# SAMV71_Xplained_Ultra_EDBG.net
KiCad netlist of a schematic drawn in Altium Designer
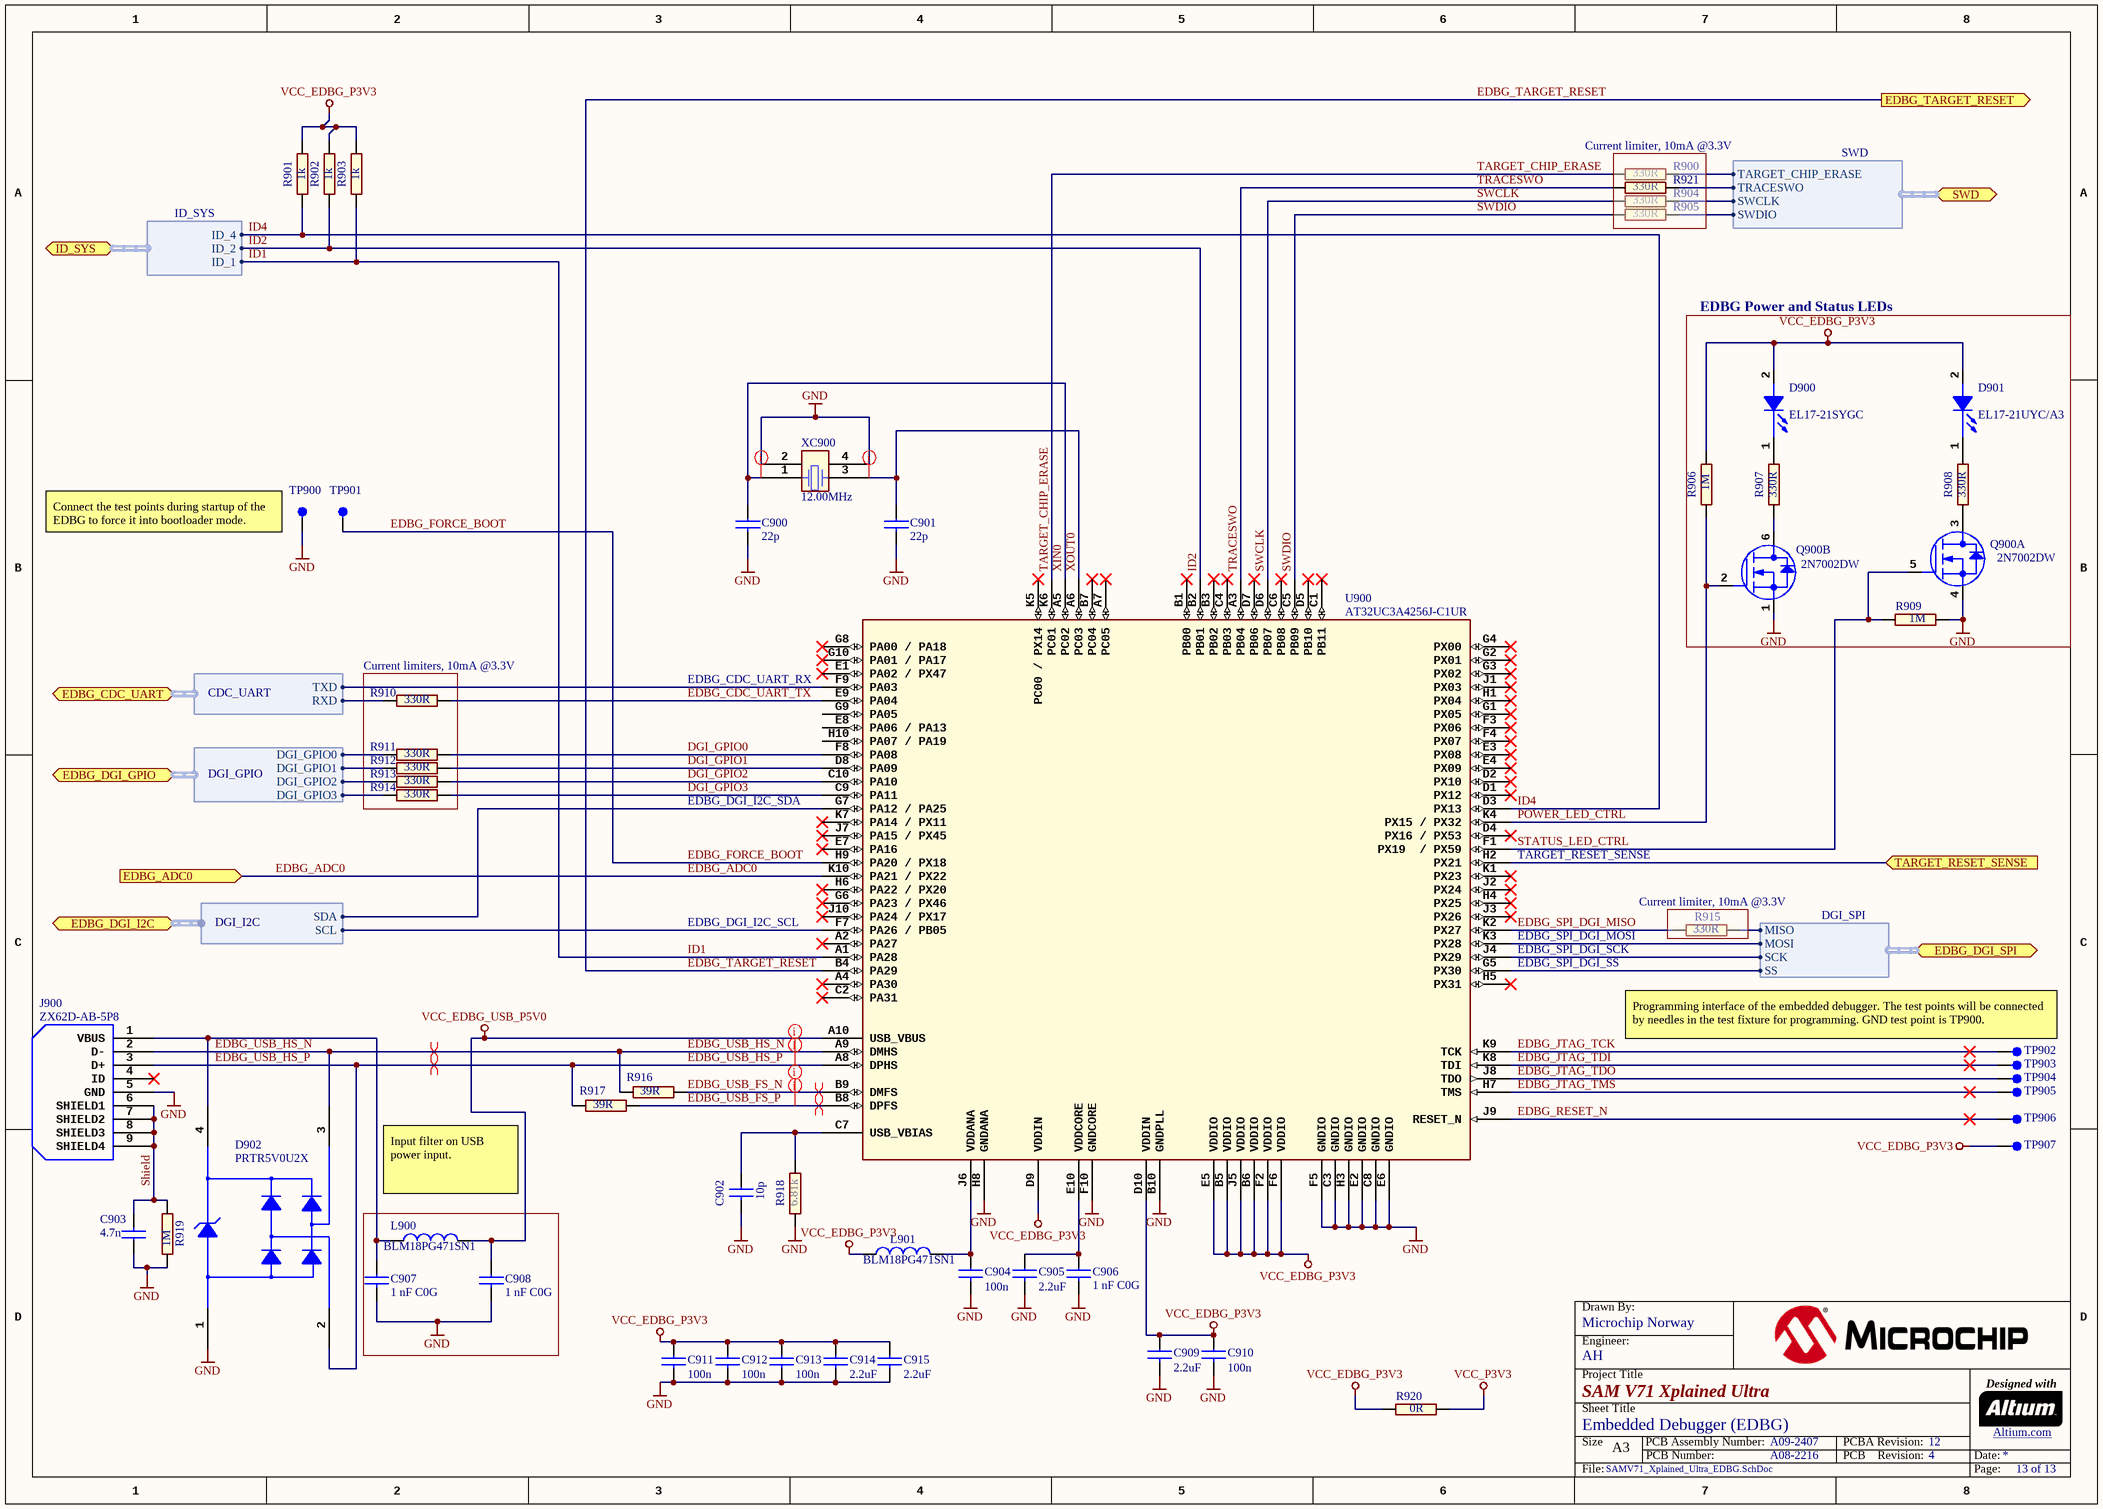
[diagram p0: SAMV71_Xplained_Ultra_EDBG.SchDoc]

(export (version "E")
  (design (tool "Eeschema 10.0.6"))
  (components
    (comp (ref "C900")
      (value "22p")
      (footprint "AP1-00053")
      (description "Ceramic capacitor, SMD 0402, NP0, 50V, +/-5%")
      (fields (field (name "TOLERANCE") "50V, +/-5%") (field (name "MANUFACTURER") "YAGEO CORP"))
      (libsource (lib "AltiumDbLib") (part "CAP-NONPOL"))
    )
    (comp (ref "C901")
      (value "22p")
      (footprint "AP1-00053")
      (description "Ceramic capacitor, SMD 0402, NP0, 50V, +/-5%")
      (fields (field (name "TOLERANCE") "50V, +/-5%") (field (name "MANUFACTURER") "YAGEO CORP"))
      (libsource (lib "AltiumDbLib") (part "CAP-NONPOL"))
    )
    (comp (ref "C902")
      (value "10p")
      (footprint "AP1-00053")
      (description "Ceramic capacitor, SMD 0402, NP0, 50V, +/-5%")
      (fields (field (name "TOLERANCE") "50V, +/-5%") (field (name "MANUFACTURER") "AVX"))
      (libsource (lib "AltiumDbLib") (part "CAP-NONPOL"))
    )
    (comp (ref "C903")
      (value "4.7n")
      (footprint "AP1-00053")
      (description "Ceramic capacitor, SMD 0402, X7R, 25V, +/-10%")
      (fields (field (name "TOLERANCE") "25V, +/-10%") (field (name "MANUFACTURER") "PHYCOMP"))
      (libsource (lib "AltiumDbLib") (part "CAP-NONPOL"))
    )
    (comp (ref "C904")
      (value "100n")
      (footprint "AP1-00053")
      (description "Ceramic capacitor, SMD 0402, X7R, 16V, +/-10%")
      (fields (field (name "TOLERANCE") "16V, +/-10%") (field (name "MANUFACTURER") "Kemet"))
      (libsource (lib "AltiumDbLib") (part "CAP-NONPOL"))
    )
    (comp (ref "C905")
      (value "2.2uF")
      (footprint "AP1-00053")
      (description "Ceramic capacitor, SMD 0402, X5R, 6.3V, +/-20%")
      (fields (field (name "TOLERANCE") "Â±20%") (field (name "MANUFACTURER") "Kemet"))
      (libsource (lib "AltiumDbLib") (part "CAP-NONPOL"))
    )
    (comp (ref "C906")
      (value "1 nF C0G")
      (footprint "AP1-00053")
      (description "Ceramic capacitor, SMD 0402, C0G, 50V, +/-5%")
      (fields (field (name "TOLERANCE") "5%") (field (name "MANUFACTURER") "Murata"))
      (libsource (lib "AltiumDbLib") (part "CAP-NONPOL"))
    )
    (comp (ref "C907")
      (value "1 nF C0G")
      (footprint "AP1-00053")
      (description "Ceramic capacitor, SMD 0402, C0G, 50V, +/-5%")
      (fields (field (name "TOLERANCE") "5%") (field (name "MANUFACTURER") "Murata"))
      (libsource (lib "AltiumDbLib") (part "CAP-NONPOL"))
    )
    (comp (ref "C908")
      (value "1 nF C0G")
      (footprint "AP1-00053")
      (description "Ceramic capacitor, SMD 0402, C0G, 50V, +/-5%")
      (fields (field (name "TOLERANCE") "5%") (field (name "MANUFACTURER") "Murata"))
      (libsource (lib "AltiumDbLib") (part "CAP-NONPOL"))
    )
    (comp (ref "C909")
      (value "2.2uF")
      (footprint "AP1-00053")
      (description "Ceramic capacitor, SMD 0402, X5R, 6.3V, +/-20%")
      (fields (field (name "TOLERANCE") "Â±20%") (field (name "MANUFACTURER") "Kemet"))
      (libsource (lib "AltiumDbLib") (part "CAP-NONPOL"))
    )
    (comp (ref "C910")
      (value "100n")
      (footprint "AP1-00053")
      (description "Ceramic capacitor, SMD 0402, X7R, 16V, +/-10%")
      (fields (field (name "TOLERANCE") "16V, +/-10%") (field (name "MANUFACTURER") "Kemet"))
      (libsource (lib "AltiumDbLib") (part "CAP-NONPOL"))
    )
    (comp (ref "C911")
      (value "100n")
      (footprint "AP1-00053")
      (description "Ceramic capacitor, SMD 0402, X7R, 16V, +/-10%")
      (fields (field (name "TOLERANCE") "16V, +/-10%") (field (name "MANUFACTURER") "Kemet"))
      (libsource (lib "AltiumDbLib") (part "CAP-NONPOL"))
    )
    (comp (ref "C912")
      (value "100n")
      (footprint "AP1-00053")
      (description "Ceramic capacitor, SMD 0402, X7R, 16V, +/-10%")
      (fields (field (name "TOLERANCE") "16V, +/-10%") (field (name "MANUFACTURER") "Kemet"))
      (libsource (lib "AltiumDbLib") (part "CAP-NONPOL"))
    )
    (comp (ref "C913")
      (value "100n")
      (footprint "AP1-00053")
      (description "Ceramic capacitor, SMD 0402, X7R, 16V, +/-10%")
      (fields (field (name "TOLERANCE") "16V, +/-10%") (field (name "MANUFACTURER") "Kemet"))
      (libsource (lib "AltiumDbLib") (part "CAP-NONPOL"))
    )
    (comp (ref "C914")
      (value "2.2uF")
      (footprint "AP1-00053")
      (description "Ceramic capacitor, SMD 0402, X5R, 6.3V, +/-20%")
      (fields (field (name "TOLERANCE") "Â±20%") (field (name "MANUFACTURER") "Kemet"))
      (libsource (lib "AltiumDbLib") (part "CAP-NONPOL"))
    )
    (comp (ref "C915")
      (value "2.2uF")
      (footprint "AP1-00053")
      (description "Ceramic capacitor, SMD 0402, X5R, 6.3V, +/-20%")
      (fields (field (name "TOLERANCE") "Â±20%") (field (name "MANUFACTURER") "Kemet"))
      (libsource (lib "AltiumDbLib") (part "CAP-NONPOL"))
    )
    (comp (ref "D900")
      (value "EL17-21SYGC")
      (footprint "AP4-00013")
      (description "LED, Green, Wave length=575nm, SMD 0805, ±70°")
      (fields (field (name "MANUFACTURER") "Everlight"))
      (libsource (lib "AltiumDbLib") (part "LED_12"))
    )
    (comp (ref "D901")
      (value "EL17-21UYC/A3")
      (footprint "AP4-00013")
      (description "LED, Yellow, Wave length=591nm, SMD 0805, ±70°")
      (fields (field (name "MANUFACTURER") "Everlight") (field (name "MPN") "17-21UYC/S530-A3/TR8"))
      (libsource (lib "AltiumDbLib") (part "LED_12"))
    )
    (comp (ref "D902")
      (value "PRTR5V0U2X")
      (footprint "AP4-00001")
      (description "Double rail-to-rail USB ESD protection diode")
      (fields (field (name "MANUFACTURER") "NXP"))
      (libsource (lib "AltiumDbLib") (part "PRTR5V0U2X"))
    )
    (comp (ref "J900")
      (value "ZX62D-AB-5P8")
      (footprint "AP8-00852")
      (description "Micro USB AB Connector, Standard SMT + DIP")
      (fields (field (name "MANUFACTURER") "HIROSE") (field (name "MPN") "ZX62D-AB-5P8(30)"))
      (libsource (lib "AltiumDbLib") (part "USB_AB"))
    )
    (comp (ref "L900")
      (value "BLM18PG471SN1")
      (footprint "AP3-00005")
      (description "SMD RF inductor 0603. Z=470Ohm (@100MHz), Max R(dc)=0.65Ohm, Max current=1A")
      (fields (field (name "MANUFACTURER") "Murata"))
      (libsource (lib "AltiumDbLib") (part "INDUCTOR"))
    )
    (comp (ref "L901")
      (value "BLM18PG471SN1")
      (footprint "AP3-00005")
      (description "SMD RF inductor 0603. Z=470Ohm (@100MHz), Max R(dc)=0.65Ohm, Max current=1A")
      (fields (field (name "MANUFACTURER") "Murata"))
      (libsource (lib "AltiumDbLib") (part "INDUCTOR"))
    )
    (comp (ref "Q900")
      (value "2N7002DW")
      (footprint "AP5-00001")
      (description "Dual N-Channel MOSFET, 60V, 115mA cont,RDS(ON) < 7.5 Ohm @50mA@5V, SOT-363")
      (fields
        (field (name "MANUFACTURER") "Fairchild")
        (field (name "Comment") "Same as 2N7002 but with two MOSFETs in one package")
      )
      (libsource (lib "AltiumDbLib") (part "MOSFET_DUAL_N_S2G2D1S1G1D2"))
    )
    (comp (ref "R900")
      (value "330R")
      (footprint "AP2-00000")
      (description "Thick film resistor, SMD 0402, 1/16W, 1%")
      (fields (field (name "TOLERANCE") "1 %") (field (name "MANUFACTURER") "ASJ"))
      (libsource (lib "") (part "R2_2"))
    )
    (comp (ref "R901")
      (value "1k")
      (footprint "AP2-00000")
      (description "Thick film resistor, SMD 0402, 1/16W, 1%")
      (fields (field (name "TOLERANCE") "1 %") (field (name "MANUFACTURER") "ASJ"))
      (libsource (lib "AltiumDbLib") (part "R2"))
    )
    (comp (ref "R902")
      (value "1k")
      (footprint "AP2-00000")
      (description "Thick film resistor, SMD 0402, 1/16W, 1%")
      (fields (field (name "TOLERANCE") "1 %") (field (name "MANUFACTURER") "ASJ"))
      (libsource (lib "AltiumDbLib") (part "R2"))
    )
    (comp (ref "R903")
      (value "1k")
      (footprint "AP2-00000")
      (description "Thick film resistor, SMD 0402, 1/16W, 1%")
      (fields (field (name "TOLERANCE") "1 %") (field (name "MANUFACTURER") "ASJ"))
      (libsource (lib "AltiumDbLib") (part "R2"))
    )
    (comp (ref "R904")
      (value "330R")
      (footprint "AP2-00000")
      (description "Thick film resistor, SMD 0402, 1/16W, 1%")
      (fields (field (name "TOLERANCE") "1 %") (field (name "MANUFACTURER") "ASJ"))
      (libsource (lib "") (part "R2_2"))
    )
    (comp (ref "R905")
      (value "330R")
      (footprint "AP2-00000")
      (description "Thick film resistor, SMD 0402, 1/16W, 1%")
      (fields (field (name "TOLERANCE") "1 %") (field (name "MANUFACTURER") "ASJ"))
      (libsource (lib "") (part "R2_2"))
    )
    (comp (ref "R906")
      (value "1M")
      (footprint "AP2-00000")
      (description "Thick film resistor, SMD 0402, 1/16W, 1%")
      (fields (field (name "TOLERANCE") "1 %") (field (name "MANUFACTURER") "ASJ"))
      (libsource (lib "AltiumDbLib") (part "R2"))
    )
    (comp (ref "R907")
      (value "330R")
      (footprint "AP2-00000")
      (description "Thick film resistor, SMD 0402, 1/16W, 1%")
      (fields (field (name "TOLERANCE") "1 %") (field (name "MANUFACTURER") "ASJ"))
      (libsource (lib "AltiumDbLib") (part "R2"))
    )
    (comp (ref "R908")
      (value "330R")
      (footprint "AP2-00000")
      (description "Thick film resistor, SMD 0402, 1/16W, 1%")
      (fields (field (name "TOLERANCE") "1 %") (field (name "MANUFACTURER") "ASJ"))
      (libsource (lib "AltiumDbLib") (part "R2"))
    )
    (comp (ref "R909")
      (value "1M")
      (footprint "AP2-00000")
      (description "Thick film resistor, SMD 0402, 1/16W, 1%")
      (fields (field (name "TOLERANCE") "1 %") (field (name "MANUFACTURER") "ASJ"))
      (libsource (lib "") (part "R2_4"))
    )
    (comp (ref "R910")
      (value "330R")
      (footprint "AP2-00000")
      (description "Thick film resistor, SMD 0402, 1/16W, 1%")
      (fields (field (name "TOLERANCE") "1 %") (field (name "MANUFACTURER") "ASJ"))
      (libsource (lib "") (part "R2_2"))
    )
    (comp (ref "R911")
      (value "330R")
      (footprint "AP2-00000")
      (description "Thick film resistor, SMD 0402, 1/16W, 1%")
      (fields (field (name "TOLERANCE") "1 %") (field (name "MANUFACTURER") "ASJ"))
      (libsource (lib "") (part "R2_2"))
    )
    (comp (ref "R912")
      (value "330R")
      (footprint "AP2-00000")
      (description "Thick film resistor, SMD 0402, 1/16W, 1%")
      (fields (field (name "TOLERANCE") "1 %") (field (name "MANUFACTURER") "ASJ"))
      (libsource (lib "") (part "R2_2"))
    )
    (comp (ref "R913")
      (value "330R")
      (footprint "AP2-00000")
      (description "Thick film resistor, SMD 0402, 1/16W, 1%")
      (fields (field (name "TOLERANCE") "1 %") (field (name "MANUFACTURER") "ASJ"))
      (libsource (lib "") (part "R2_2"))
    )
    (comp (ref "R914")
      (value "330R")
      (footprint "AP2-00000")
      (description "Thick film resistor, SMD 0402, 1/16W, 1%")
      (fields (field (name "TOLERANCE") "1 %") (field (name "MANUFACTURER") "ASJ"))
      (libsource (lib "") (part "R2_2"))
    )
    (comp (ref "R915")
      (value "330R")
      (footprint "AP2-00000")
      (description "Thick film resistor, SMD 0402, 1/16W, 1%")
      (fields (field (name "TOLERANCE") "1 %") (field (name "MANUFACTURER") "ASJ"))
      (libsource (lib "") (part "R2_2"))
    )
    (comp (ref "R916")
      (value "39R")
      (footprint "AP2-00011")
      (description "Thick film resistor, SMD 0402, 1/16W, 1%")
      (fields (field (name "TOLERANCE") "1 %") (field (name "MANUFACTURER") "ASJ"))
      (libsource (lib "") (part "R2_1"))
    )
    (comp (ref "R917")
      (value "39R")
      (footprint "AP2-00011")
      (description "Thick film resistor, SMD 0402, 1/16W, 1%")
      (fields (field (name "TOLERANCE") "1 %") (field (name "MANUFACTURER") "ASJ"))
      (libsource (lib "") (part "R2_1"))
    )
    (comp (ref "R918")
      (value "6.81k")
      (footprint "AP2-00011")
      (description "Thick film resistor, SMD 0402, 1/16W, 1%")
      (fields (field (name "TOLERANCE") "1%") (field (name "MANUFACTURER") "vishay"))
      (libsource (lib "AltiumDbLib") (part "R2"))
    )
    (comp (ref "R919")
      (value "1M")
      (footprint "AP2-00011")
      (description "Thick film resistor, SMD 0402, 1/16W, 1%")
      (fields (field (name "TOLERANCE") "1 %") (field (name "MANUFACTURER") "ASJ"))
      (libsource (lib "") (part "R2_3"))
    )
    (comp (ref "R920")
      (value "0R")
      (footprint "AP2-00000")
      (description "Thick film resistor, SMD 0402, 1/16W, 1%")
      (fields (field (name "TOLERANCE") "1 %") (field (name "MANUFACTURER") "(n/a)"))
      (libsource (lib "") (part "R2_2"))
    )
    (comp (ref "R921")
      (value "330R")
      (footprint "AP2-00000")
      (description "Thick film resistor, SMD 0402, 1/16W, 1%")
      (fields (field (name "TOLERANCE") "1 %") (field (name "MANUFACTURER") "ASJ"))
      (libsource (lib "") (part "R2_2"))
    )
    (comp (ref "TP900")
      (value "~")
      (footprint "AP8-00010")
      (description "Single SMD testpad")
      (libsource (lib "AltiumDbLib") (part "TESTPOINT"))
    )
    (comp (ref "TP901")
      (value "~")
      (footprint "AP8-00010")
      (description "Single SMD testpad")
      (libsource (lib "AltiumDbLib") (part "TESTPOINT"))
    )
    (comp (ref "TP902")
      (value "~")
      (footprint "AP8-00010")
      (description "Single SMD testpad")
      (libsource (lib "AltiumDbLib") (part "TESTPOINT"))
    )
    (comp (ref "TP903")
      (value "~")
      (footprint "AP8-00010")
      (description "Single SMD testpad")
      (libsource (lib "AltiumDbLib") (part "TESTPOINT"))
    )
    (comp (ref "TP904")
      (value "~")
      (footprint "AP8-00010")
      (description "Single SMD testpad")
      (libsource (lib "AltiumDbLib") (part "TESTPOINT"))
    )
    (comp (ref "TP905")
      (value "~")
      (footprint "AP8-00010")
      (description "Single SMD testpad")
      (libsource (lib "AltiumDbLib") (part "TESTPOINT"))
    )
    (comp (ref "TP906")
      (value "~")
      (footprint "AP8-00010")
      (description "Single SMD testpad")
      (libsource (lib "AltiumDbLib") (part "TESTPOINT"))
    )
    (comp (ref "TP907")
      (value "~")
      (footprint "AP8-00010")
      (description "Single SMD testpad")
      (libsource (lib "AltiumDbLib") (part "TESTPOINT"))
    )
    (comp (ref "U900")
      (value "AT32UC3A4256J-C1UR")
      (footprint "AP6-00206")
      (description "AVR 32-bit RISC MCU")
      (fields (field (name "MANUFACTURER") "ATMEL") (field (name "Comment") "100 ball VFBGA"))
      (libsource (lib "AltiumDbLib") (part "AT32UC3A4_VFBGA"))
    )
    (comp (ref "XC900")
      (value "12.00MHz")
      (footprint "AP7-00039")
      (description "Fox FQ5032B 12.0MHz SMD crystal 738B-12")
      (fields (field (name "TOLERANCE") "Â±30ppm") (field (name "MANUFACTURER") "Fox  Electronics"))
      (libsource (lib "AltiumDbLib") (part "CRYSTAL1324"))
    )
  )
  (nets
    (net (code "7") (name "/DGI_GPIO0") (class "Default")
      (node (ref "R911") (pin "2") (pinfunction "2_2") (pintype "passive"))
      (node (ref "U900") (pin "F8") (pinfunction "PA08_F8") (pintype "bidirectional"))
    )
    (net (code "8") (name "/DGI_GPIO1") (class "Default")
      (node (ref "R912") (pin "2") (pinfunction "2_2") (pintype "passive"))
      (node (ref "U900") (pin "D8") (pinfunction "PA09_D8") (pintype "bidirectional"))
    )
    (net (code "9") (name "/DGI_GPIO2") (class "Default")
      (node (ref "R913") (pin "2") (pinfunction "2_2") (pintype "passive"))
      (node (ref "U900") (pin "C10") (pinfunction "PA10_C10") (pintype "bidirectional"))
    )
    (net (code "10") (name "/DGI_GPIO3") (class "Default")
      (node (ref "R914") (pin "2") (pinfunction "2_2") (pintype "passive"))
      (node (ref "U900") (pin "C9") (pinfunction "PA11_C9") (pintype "bidirectional"))
    )
    (net (code "11") (name "/EDBG_ADC0") (class "Default")
      (node (ref "U900") (pin "K10") (pinfunction "PA21_/_PX22_K10") (pintype "bidirectional"))
    )
    (net (code "12") (name "/EDBG_CDC_UART_TX") (class "Default")
      (node (ref "R910") (pin "2") (pinfunction "2_2") (pintype "passive"))
      (node (ref "U900") (pin "E9") (pinfunction "PA04_E9") (pintype "bidirectional"))
    )
    (net (code "13") (name "/EDBG_FORCE_BOOT") (class "Default")
      (node (ref "TP901") (pin "1") (pinfunction "1_1") (pintype "passive"))
      (node (ref "U900") (pin "H9") (pinfunction "PA20_/_PX18_H9") (pintype "bidirectional"))
    )
    (net (code "14") (name "/EDBG_JTAG_TCK") (class "Default")
      (node (ref "TP902") (pin "1") (pinfunction "1_1") (pintype "passive"))
      (node (ref "U900") (pin "K9") (pinfunction "TCK_K9") (pintype "input"))
    )
    (net (code "15") (name "/EDBG_JTAG_TDI") (class "Default")
      (node (ref "TP903") (pin "1") (pinfunction "1_1") (pintype "passive"))
      (node (ref "U900") (pin "K8") (pinfunction "TDI_K8") (pintype "input"))
    )
    (net (code "16") (name "/EDBG_JTAG_TDO") (class "Default")
      (node (ref "TP904") (pin "1") (pinfunction "1_1") (pintype "passive"))
      (node (ref "U900") (pin "J8") (pinfunction "TDO_J8") (pintype "output"))
    )
    (net (code "17") (name "/EDBG_JTAG_TMS") (class "Default")
      (node (ref "TP905") (pin "1") (pinfunction "1_1") (pintype "passive"))
      (node (ref "U900") (pin "H7") (pinfunction "TMS_H7") (pintype "input"))
    )
    (net (code "18") (name "/EDBG_RESET_N") (class "Default")
      (node (ref "TP906") (pin "1") (pinfunction "1_1") (pintype "passive"))
      (node (ref "U900") (pin "J9") (pinfunction "RESET_N_J9") (pintype "input"))
    )
    (net (code "19") (name "/EDBG_SPI_DGI_MISO") (class "Default")
      (node (ref "R915") (pin "1") (pinfunction "1_1") (pintype "passive"))
      (node (ref "U900") (pin "K2") (pinfunction "PX27_K2") (pintype "bidirectional"))
    )
    (net (code "20") (name "/EDBG_TARGET_RESET") (class "Default")
      (node (ref "U900") (pin "B4") (pinfunction "PA29_B4") (pintype "bidirectional"))
    )
    (net (code "21") (name "/EDBG_USB_FS_N") (class "Default")
      (node (ref "R916") (pin "2") (pinfunction "2_2") (pintype "passive"))
      (node (ref "U900") (pin "B9") (pinfunction "DMFS_B9") (pintype "bidirectional"))
    )
    (net (code "22") (name "/EDBG_USB_FS_P") (class "Default")
      (node (ref "R917") (pin "2") (pinfunction "2_2") (pintype "passive"))
      (node (ref "U900") (pin "B8") (pinfunction "DPFS_B8") (pintype "bidirectional"))
    )
    (net (code "23") (name "/EDBG_USB_HS_N") (class "Default")
      (node (ref "D902") (pin "3") (pinfunction "I/O_2_3") (pintype "passive"))
      (node (ref "J900") (pin "2") (pinfunction "D-_2") (pintype "passive"))
      (node (ref "R916") (pin "1") (pinfunction "1_1") (pintype "passive"))
      (node (ref "U900") (pin "A9") (pinfunction "DMHS_A9") (pintype "bidirectional"))
    )
    (net (code "24") (name "/EDBG_USB_HS_P") (class "Default")
      (node (ref "D902") (pin "2") (pinfunction "I/O_1_2") (pintype "passive"))
      (node (ref "J900") (pin "3") (pinfunction "D+_3") (pintype "passive"))
      (node (ref "R917") (pin "1") (pinfunction "1_1") (pintype "passive"))
      (node (ref "U900") (pin "A8") (pinfunction "DPHS_A8") (pintype "bidirectional"))
    )
    (net (code "25") (name "/ID1") (class "Default")
      (node (ref "R903") (pin "1") (pinfunction "1_1") (pintype "passive"))
      (node (ref "U900") (pin "A1") (pinfunction "PA28_A1") (pintype "bidirectional"))
    )
    (net (code "26") (name "/ID2") (class "Default")
      (node (ref "R902") (pin "1") (pinfunction "1_1") (pintype "passive"))
      (node (ref "U900") (pin "B2") (pinfunction "PB01_B2") (pintype "bidirectional"))
    )
    (net (code "27") (name "/ID4") (class "Default")
      (node (ref "R901") (pin "1") (pinfunction "1_1") (pintype "passive"))
      (node (ref "U900") (pin "D3") (pinfunction "PX13_D3") (pintype "bidirectional"))
    )
    (net (code "28") (name "/MISO") (class "Default")
      (node (ref "R915") (pin "2") (pinfunction "2_2") (pintype "passive"))
    )
    (net (code "29") (name "/MOSI") (class "Default")
      (node (ref "U900") (pin "K3") (pinfunction "PX28_K3") (pintype "bidirectional"))
    )
    (net (code "30") (name "/POWER_LED_CTRL") (class "Default")
      (node (ref "Q900") (pin "2") (pinfunction "G2_2") (pintype "passive"))
      (node (ref "R906") (pin "1") (pinfunction "1_1") (pintype "passive"))
      (node (ref "U900") (pin "K4") (pinfunction "PX15_/_PX32_K4") (pintype "bidirectional"))
    )
    (net (code "31") (name "/RXD") (class "Default")
      (node (ref "R910") (pin "1") (pinfunction "1_1") (pintype "passive"))
    )
    (net (code "32") (name "/SCK") (class "Default")
      (node (ref "U900") (pin "J4") (pinfunction "PX29_J4") (pintype "bidirectional"))
    )
    (net (code "33") (name "/SCL") (class "Default")
      (node (ref "U900") (pin "F7") (pinfunction "PA26_/_PB05_F7") (pintype "bidirectional"))
    )
    (net (code "34") (name "/SDA") (class "Default")
      (node (ref "U900") (pin "G7") (pinfunction "PA12_/_PA25_G7") (pintype "bidirectional"))
    )
    (net (code "35") (name "/SS") (class "Default")
      (node (ref "U900") (pin "G5") (pinfunction "PX30_G5") (pintype "bidirectional"))
    )
    (net (code "36") (name "/STATUS_LED_CTRL") (class "Default")
      (node (ref "Q900") (pin "5") (pinfunction "G1_5") (pintype "passive"))
      (node (ref "R909") (pin "2") (pinfunction "2_2") (pintype "passive"))
      (node (ref "U900") (pin "F1") (pinfunction "PX19__/_PX59_F1") (pintype "bidirectional"))
    )
    (net (code "37") (name "/SWCLK") (class "Default")
      (node (ref "R904") (pin "1") (pinfunction "1_1") (pintype "passive"))
      (node (ref "U900") (pin "D6") (pinfunction "PB07_D6") (pintype "bidirectional"))
    )
    (net (code "38") (name "/SWDIO") (class "Default")
      (node (ref "R905") (pin "1") (pinfunction "1_1") (pintype "passive"))
      (node (ref "U900") (pin "C5") (pinfunction "PB09_C5") (pintype "bidirectional"))
    )
    (net (code "39") (name "/Shield") (class "Default")
      (node (ref "C903") (pin "2") (pinfunction "2_2") (pintype "passive"))
      (node (ref "J900") (pin "6") (pinfunction "SHIELD1_6") (pintype "passive"))
      (node (ref "J900") (pin "7") (pinfunction "SHIELD2_7") (pintype "passive"))
      (node (ref "J900") (pin "8") (pinfunction "SHIELD3_8") (pintype "passive"))
      (node (ref "J900") (pin "9") (pinfunction "SHIELD4_9") (pintype "passive"))
      (node (ref "R919") (pin "2") (pinfunction "2_2") (pintype "passive"))
    )
    (net (code "40") (name "/TARGET_CHIP_ERASE") (class "Default")
      (node (ref "R900") (pin "1") (pinfunction "1_1") (pintype "passive"))
      (node (ref "U900") (pin "K6") (pinfunction "PC01_K6") (pintype "bidirectional"))
    )
    (net (code "41") (name "/TARGET_RESET_SENSE") (class "Default")
      (node (ref "U900") (pin "H2") (pinfunction "PX21_H2") (pintype "bidirectional"))
    )
    (net (code "42") (name "/TRACESWO") (class "Default")
      (node (ref "R921") (pin "1") (pinfunction "1_1") (pintype "passive"))
      (node (ref "U900") (pin "A3") (pinfunction "PB04_A3") (pintype "bidirectional"))
    )
    (net (code "43") (name "/TXD") (class "Default")
      (node (ref "U900") (pin "F9") (pinfunction "PA03_F9") (pintype "bidirectional"))
    )
    (net (code "44") (name "/XIN0") (class "Default")
      (node (ref "C900") (pin "1") (pinfunction "1_1") (pintype "passive"))
      (node (ref "U900") (pin "A5") (pinfunction "PC02_A5") (pintype "bidirectional"))
      (node (ref "XC900") (pin "1") (pinfunction "1_1") (pintype "passive"))
    )
    (net (code "45") (name "/XOUT0") (class "Default")
      (node (ref "C901") (pin "1") (pinfunction "1_1") (pintype "passive"))
      (node (ref "U900") (pin "A6") (pinfunction "PC03_A6") (pintype "bidirectional"))
      (node (ref "XC900") (pin "3") (pinfunction "3_3") (pintype "passive"))
    )
    (net (code "52") (name "GND") (class "Default")
      (node (ref "C900") (pin "2") (pinfunction "2_2") (pintype "passive"))
      (node (ref "C901") (pin "2") (pinfunction "2_2") (pintype "passive"))
      (node (ref "C902") (pin "2") (pinfunction "2_2") (pintype "passive"))
      (node (ref "C903") (pin "1") (pinfunction "1_1") (pintype "passive"))
      (node (ref "C904") (pin "2") (pinfunction "2_2") (pintype "passive"))
      (node (ref "C905") (pin "2") (pinfunction "2_2") (pintype "passive"))
      (node (ref "C906") (pin "2") (pinfunction "2_2") (pintype "passive"))
      (node (ref "C907") (pin "2") (pinfunction "2_2") (pintype "passive"))
      (node (ref "C908") (pin "2") (pinfunction "2_2") (pintype "passive"))
      (node (ref "C909") (pin "2") (pinfunction "2_2") (pintype "passive"))
      (node (ref "C910") (pin "2") (pinfunction "2_2") (pintype "passive"))
      (node (ref "C911") (pin "2") (pinfunction "2_2") (pintype "passive"))
      (node (ref "C912") (pin "2") (pinfunction "2_2") (pintype "passive"))
      (node (ref "C913") (pin "2") (pinfunction "2_2") (pintype "passive"))
      (node (ref "C914") (pin "2") (pinfunction "2_2") (pintype "passive"))
      (node (ref "C915") (pin "2") (pinfunction "2_2") (pintype "passive"))
      (node (ref "D902") (pin "1") (pinfunction "GND_1") (pintype "passive"))
      (node (ref "J900") (pin "5") (pinfunction "GND_5") (pintype "passive"))
      (node (ref "Q900") (pin "1") (pinfunction "S2_1") (pintype "passive"))
      (node (ref "Q900") (pin "4") (pinfunction "S1_4") (pintype "passive"))
      (node (ref "R909") (pin "1") (pinfunction "1_1") (pintype "passive"))
      (node (ref "R918") (pin "1") (pinfunction "1_1") (pintype "passive"))
      (node (ref "R919") (pin "1") (pinfunction "1_1") (pintype "passive"))
      (node (ref "TP900") (pin "1") (pinfunction "1_1") (pintype "passive"))
      (node (ref "U900") (pin "B10") (pinfunction "GNDPLL_B10") (pintype "power_in"))
      (node (ref "U900") (pin "C3") (pinfunction "GNDIO_C3") (pintype "power_in"))
      (node (ref "U900") (pin "C8") (pinfunction "GNDIO_C8") (pintype "power_in"))
      (node (ref "U900") (pin "E2") (pinfunction "GNDIO_E2") (pintype "power_in"))
      (node (ref "U900") (pin "E6") (pinfunction "GNDIO_E6") (pintype "power_in"))
      (node (ref "U900") (pin "F10") (pinfunction "GNDCORE_F10") (pintype "power_in"))
      (node (ref "U900") (pin "F5") (pinfunction "GNDIO_F5") (pintype "power_in"))
      (node (ref "U900") (pin "H3") (pinfunction "GNDIO_H3") (pintype "power_in"))
      (node (ref "U900") (pin "H8") (pinfunction "GNDANA_H8") (pintype "power_in"))
      (node (ref "XC900") (pin "2") (pinfunction "2_2") (pintype "passive"))
      (node (ref "XC900") (pin "4") (pinfunction "4_4") (pintype "passive"))
    )
    (net (code "53") (name "Net-(D900-CATHODE)") (class "Default")
      (node (ref "D900") (pin "1") (pinfunction "CATHODE_1") (pintype "passive"))
      (node (ref "R907") (pin "2") (pinfunction "2_2") (pintype "passive"))
    )
    (net (code "54") (name "Net-(D901-CATHODE)") (class "Default")
      (node (ref "D901") (pin "1") (pinfunction "CATHODE_1") (pintype "passive"))
      (node (ref "R908") (pin "2") (pinfunction "2_2") (pintype "passive"))
    )
    (net (code "55") (name "Net-(D902-VCC)") (class "Default")
      (node (ref "C907") (pin "1") (pinfunction "1_1") (pintype "passive"))
      (node (ref "D902") (pin "4") (pinfunction "VCC_4") (pintype "passive"))
      (node (ref "J900") (pin "1") (pinfunction "VBUS_1") (pintype "passive"))
      (node (ref "L900") (pin "1") (pinfunction "1_1") (pintype "passive"))
    )
    (net (code "56") (name "Net-(Q900A-D1)") (class "Default")
      (node (ref "Q900") (pin "3") (pinfunction "D1_3") (pintype "passive"))
      (node (ref "R908") (pin "1") (pinfunction "1_1") (pintype "passive"))
    )
    (net (code "57") (name "Net-(Q900B-D2)") (class "Default")
      (node (ref "Q900") (pin "6") (pinfunction "D2_6") (pintype "passive"))
      (node (ref "R907") (pin "1") (pinfunction "1_1") (pintype "passive"))
    )
    (net (code "58") (name "Net-(U900-USB_VBIAS)") (class "Default")
      (node (ref "C902") (pin "1") (pinfunction "1_1") (pintype "passive"))
      (node (ref "R918") (pin "2") (pinfunction "2_2") (pintype "passive"))
      (node (ref "U900") (pin "C7") (pinfunction "USB_VBIAS_C7") (pintype "power_in"))
    )
    (net (code "59") (name "Net-(U900-VDDANA)") (class "Default")
      (node (ref "C904") (pin "1") (pinfunction "1_1") (pintype "passive"))
      (node (ref "L901") (pin "2") (pinfunction "2_2") (pintype "passive"))
      (node (ref "U900") (pin "J6") (pinfunction "VDDANA_J6") (pintype "power_in"))
    )
    (net (code "60") (name "Net-(U900-VDDCORE)") (class "Default")
      (node (ref "C905") (pin "1") (pinfunction "1_1") (pintype "passive"))
      (node (ref "C906") (pin "1") (pinfunction "1_1") (pintype "passive"))
      (node (ref "U900") (pin "E10") (pinfunction "VDDCORE_E10") (pintype "power_in"))
    )
    (net (code "61") (name "VCC_EDBG_P3V3") (class "Default")
      (node (ref "C909") (pin "1") (pinfunction "1_1") (pintype "passive"))
      (node (ref "C910") (pin "1") (pinfunction "1_1") (pintype "passive"))
      (node (ref "C911") (pin "1") (pinfunction "1_1") (pintype "passive"))
      (node (ref "C912") (pin "1") (pinfunction "1_1") (pintype "passive"))
      (node (ref "C913") (pin "1") (pinfunction "1_1") (pintype "passive"))
      (node (ref "C914") (pin "1") (pinfunction "1_1") (pintype "passive"))
      (node (ref "C915") (pin "1") (pinfunction "1_1") (pintype "passive"))
      (node (ref "D900") (pin "2") (pinfunction "ANODE_2") (pintype "passive"))
      (node (ref "D901") (pin "2") (pinfunction "ANODE_2") (pintype "passive"))
      (node (ref "L901") (pin "1") (pinfunction "1_1") (pintype "passive"))
      (node (ref "R901") (pin "2") (pinfunction "2_2") (pintype "passive"))
      (node (ref "R902") (pin "2") (pinfunction "2_2") (pintype "passive"))
      (node (ref "R903") (pin "2") (pinfunction "2_2") (pintype "passive"))
      (node (ref "R906") (pin "2") (pinfunction "2_2") (pintype "passive"))
      (node (ref "R920") (pin "1") (pinfunction "1_1") (pintype "passive"))
      (node (ref "TP907") (pin "1") (pinfunction "1_1") (pintype "passive"))
      (node (ref "U900") (pin "B5") (pinfunction "VDDIO_B5") (pintype "power_in"))
      (node (ref "U900") (pin "B6") (pinfunction "VDDIO_B6") (pintype "power_in"))
      (node (ref "U900") (pin "D10") (pinfunction "VDDIN_D10") (pintype "power_in"))
      (node (ref "U900") (pin "D9") (pinfunction "VDDIN_D9") (pintype "power_in"))
      (node (ref "U900") (pin "E5") (pinfunction "VDDIO_E5") (pintype "power_in"))
      (node (ref "U900") (pin "F2") (pinfunction "VDDIO_F2") (pintype "power_in"))
      (node (ref "U900") (pin "F6") (pinfunction "VDDIO_F6") (pintype "power_in"))
      (node (ref "U900") (pin "J5") (pinfunction "VDDIO_J5") (pintype "power_in"))
    )
    (net (code "62") (name "VCC_EDBG_USB_P5V0") (class "Default")
      (node (ref "C908") (pin "1") (pinfunction "1_1") (pintype "passive"))
      (node (ref "L900") (pin "2") (pinfunction "2_2") (pintype "passive"))
      (node (ref "U900") (pin "A10") (pinfunction "USB_VBUS_A10") (pintype "power_in"))
    )
    (net (code "63") (name "VCC_P3V3") (class "Default")
      (node (ref "R920") (pin "2") (pinfunction "2_2") (pintype "passive"))
    )
    (net (code "64") (name "unconnected-(J900-ID-Pad4)") (class "Default")
      (node (ref "J900") (pin "4") (pinfunction "ID_4") (pintype "passive+no_connect"))
    )
    (net (code "65") (name "unconnected-(R900-Pad2)") (class "Default")
      (node (ref "R900") (pin "2") (pinfunction "2_2") (pintype "passive"))
    )
    (net (code "66") (name "unconnected-(R904-Pad2)") (class "Default")
      (node (ref "R904") (pin "2") (pinfunction "2_2") (pintype "passive"))
    )
    (net (code "67") (name "unconnected-(R905-Pad2)") (class "Default")
      (node (ref "R905") (pin "2") (pinfunction "2_2") (pintype "passive"))
    )
    (net (code "68") (name "unconnected-(R911-Pad1)") (class "Default")
      (node (ref "R911") (pin "1") (pinfunction "1_1") (pintype "passive"))
    )
    (net (code "69") (name "unconnected-(R912-Pad1)") (class "Default")
      (node (ref "R912") (pin "1") (pinfunction "1_1") (pintype "passive"))
    )
    (net (code "70") (name "unconnected-(R913-Pad1)") (class "Default")
      (node (ref "R913") (pin "1") (pinfunction "1_1") (pintype "passive"))
    )
    (net (code "71") (name "unconnected-(R914-Pad1)") (class "Default")
      (node (ref "R914") (pin "1") (pinfunction "1_1") (pintype "passive"))
    )
    (net (code "72") (name "unconnected-(R921-Pad2)") (class "Default")
      (node (ref "R921") (pin "2") (pinfunction "2_2") (pintype "passive"))
    )
    (net (code "73") (name "unconnected-(U900-PA00_{slash}_PA18-PadG8)") (class "Default")
      (node (ref "U900") (pin "G8") (pinfunction "PA00_/_PA18_G8") (pintype "bidirectional+no_connect"))
    )
    (net (code "74") (name "unconnected-(U900-PA01_{slash}_PA17-PadG10)") (class "Default")
      (node (ref "U900") (pin "G10") (pinfunction "PA01_/_PA17_G10") (pintype "bidirectional+no_connect"))
    )
    (net (code "75") (name "unconnected-(U900-PA02_{slash}_PX47-PadE1)") (class "Default")
      (node (ref "U900") (pin "E1") (pinfunction "PA02_/_PX47_E1") (pintype "bidirectional+no_connect"))
    )
    (net (code "76") (name "unconnected-(U900-PA05-PadG9)") (class "Default")
      (node (ref "U900") (pin "G9") (pinfunction "PA05_G9") (pintype "bidirectional"))
    )
    (net (code "77") (name "unconnected-(U900-PA06_{slash}_PA13-PadE8)") (class "Default")
      (node (ref "U900") (pin "E8") (pinfunction "PA06_/_PA13_E8") (pintype "bidirectional"))
    )
    (net (code "78") (name "unconnected-(U900-PA07_{slash}_PA19-PadH10)") (class "Default")
      (node (ref "U900") (pin "H10") (pinfunction "PA07_/_PA19_H10") (pintype "bidirectional"))
    )
    (net (code "79") (name "unconnected-(U900-PA14_{slash}_PX11-PadK7)") (class "Default")
      (node (ref "U900") (pin "K7") (pinfunction "PA14_/_PX11_K7") (pintype "bidirectional+no_connect"))
    )
    (net (code "80") (name "unconnected-(U900-PA15_{slash}_PX45-PadJ7)") (class "Default")
      (node (ref "U900") (pin "J7") (pinfunction "PA15_/_PX45_J7") (pintype "bidirectional+no_connect"))
    )
    (net (code "81") (name "unconnected-(U900-PA16-PadE7)") (class "Default")
      (node (ref "U900") (pin "E7") (pinfunction "PA16_E7") (pintype "bidirectional+no_connect"))
    )
    (net (code "82") (name "unconnected-(U900-PA22_{slash}_PX20-PadH6)") (class "Default")
      (node (ref "U900") (pin "H6") (pinfunction "PA22_/_PX20_H6") (pintype "bidirectional+no_connect"))
    )
    (net (code "83") (name "unconnected-(U900-PA23_{slash}_PX46-PadG6)") (class "Default")
      (node (ref "U900") (pin "G6") (pinfunction "PA23_/_PX46_G6") (pintype "bidirectional+no_connect"))
    )
    (net (code "84") (name "unconnected-(U900-PA24_{slash}_PX17-PadJ10)") (class "Default")
      (node (ref "U900") (pin "J10") (pinfunction "PA24_/_PX17_J10") (pintype "bidirectional+no_connect"))
    )
    (net (code "85") (name "unconnected-(U900-PA27-PadA2)") (class "Default")
      (node (ref "U900") (pin "A2") (pinfunction "PA27_A2") (pintype "bidirectional+no_connect"))
    )
    (net (code "86") (name "unconnected-(U900-PA30-PadA4)") (class "Default")
      (node (ref "U900") (pin "A4") (pinfunction "PA30_A4") (pintype "bidirectional+no_connect"))
    )
    (net (code "87") (name "unconnected-(U900-PA31-PadC2)") (class "Default")
      (node (ref "U900") (pin "C2") (pinfunction "PA31_C2") (pintype "bidirectional+no_connect"))
    )
    (net (code "88") (name "unconnected-(U900-PB00-PadB1)") (class "Default")
      (node (ref "U900") (pin "B1") (pinfunction "PB00_B1") (pintype "bidirectional+no_connect"))
    )
    (net (code "89") (name "unconnected-(U900-PB02-PadB3)") (class "Default")
      (node (ref "U900") (pin "B3") (pinfunction "PB02_B3") (pintype "bidirectional+no_connect"))
    )
    (net (code "90") (name "unconnected-(U900-PB03-PadC4)") (class "Default")
      (node (ref "U900") (pin "C4") (pinfunction "PB03_C4") (pintype "bidirectional+no_connect"))
    )
    (net (code "91") (name "unconnected-(U900-PB06-PadD7)") (class "Default")
      (node (ref "U900") (pin "D7") (pinfunction "PB06_D7") (pintype "bidirectional+no_connect"))
    )
    (net (code "92") (name "unconnected-(U900-PB08-PadC6)") (class "Default")
      (node (ref "U900") (pin "C6") (pinfunction "PB08_C6") (pintype "bidirectional+no_connect"))
    )
    (net (code "93") (name "unconnected-(U900-PB10-PadD5)") (class "Default")
      (node (ref "U900") (pin "D5") (pinfunction "PB10_D5") (pintype "bidirectional+no_connect"))
    )
    (net (code "94") (name "unconnected-(U900-PB11-PadC1)") (class "Default")
      (node (ref "U900") (pin "C1") (pinfunction "PB11_C1") (pintype "bidirectional+no_connect"))
    )
    (net (code "95") (name "unconnected-(U900-PC00_{slash}_PX14-PadK5)") (class "Default")
      (node (ref "U900") (pin "K5") (pinfunction "PC00_/_PX14_K5") (pintype "bidirectional+no_connect"))
    )
    (net (code "96") (name "unconnected-(U900-PC04-PadB7)") (class "Default")
      (node (ref "U900") (pin "B7") (pinfunction "PC04_B7") (pintype "bidirectional+no_connect"))
    )
    (net (code "97") (name "unconnected-(U900-PC05-PadA7)") (class "Default")
      (node (ref "U900") (pin "A7") (pinfunction "PC05_A7") (pintype "bidirectional+no_connect"))
    )
    (net (code "98") (name "unconnected-(U900-PX00-PadG4)") (class "Default")
      (node (ref "U900") (pin "G4") (pinfunction "PX00_G4") (pintype "bidirectional+no_connect"))
    )
    (net (code "99") (name "unconnected-(U900-PX01-PadG2)") (class "Default")
      (node (ref "U900") (pin "G2") (pinfunction "PX01_G2") (pintype "bidirectional+no_connect"))
    )
    (net (code "100") (name "unconnected-(U900-PX02-PadG3)") (class "Default")
      (node (ref "U900") (pin "G3") (pinfunction "PX02_G3") (pintype "bidirectional+no_connect"))
    )
    (net (code "101") (name "unconnected-(U900-PX03-PadJ1)") (class "Default")
      (node (ref "U900") (pin "J1") (pinfunction "PX03_J1") (pintype "bidirectional+no_connect"))
    )
    (net (code "102") (name "unconnected-(U900-PX04-PadH1)") (class "Default")
      (node (ref "U900") (pin "H1") (pinfunction "PX04_H1") (pintype "bidirectional+no_connect"))
    )
    (net (code "103") (name "unconnected-(U900-PX05-PadG1)") (class "Default")
      (node (ref "U900") (pin "G1") (pinfunction "PX05_G1") (pintype "bidirectional+no_connect"))
    )
    (net (code "104") (name "unconnected-(U900-PX06-PadF3)") (class "Default")
      (node (ref "U900") (pin "F3") (pinfunction "PX06_F3") (pintype "bidirectional+no_connect"))
    )
    (net (code "105") (name "unconnected-(U900-PX07-PadF4)") (class "Default")
      (node (ref "U900") (pin "F4") (pinfunction "PX07_F4") (pintype "bidirectional+no_connect"))
    )
    (net (code "106") (name "unconnected-(U900-PX08-PadE3)") (class "Default")
      (node (ref "U900") (pin "E3") (pinfunction "PX08_E3") (pintype "bidirectional+no_connect"))
    )
    (net (code "107") (name "unconnected-(U900-PX09-PadE4)") (class "Default")
      (node (ref "U900") (pin "E4") (pinfunction "PX09_E4") (pintype "bidirectional+no_connect"))
    )
    (net (code "108") (name "unconnected-(U900-PX10-PadD2)") (class "Default")
      (node (ref "U900") (pin "D2") (pinfunction "PX10_D2") (pintype "bidirectional+no_connect"))
    )
    (net (code "109") (name "unconnected-(U900-PX12-PadD1)") (class "Default")
      (node (ref "U900") (pin "D1") (pinfunction "PX12_D1") (pintype "bidirectional+no_connect"))
    )
    (net (code "110") (name "unconnected-(U900-PX16_{slash}_PX53-PadD4)") (class "Default")
      (node (ref "U900") (pin "D4") (pinfunction "PX16_/_PX53_D4") (pintype "bidirectional+no_connect"))
    )
    (net (code "111") (name "unconnected-(U900-PX23-PadK1)") (class "Default")
      (node (ref "U900") (pin "K1") (pinfunction "PX23_K1") (pintype "bidirectional+no_connect"))
    )
    (net (code "112") (name "unconnected-(U900-PX24-PadJ2)") (class "Default")
      (node (ref "U900") (pin "J2") (pinfunction "PX24_J2") (pintype "bidirectional+no_connect"))
    )
    (net (code "113") (name "unconnected-(U900-PX25-PadH4)") (class "Default")
      (node (ref "U900") (pin "H4") (pinfunction "PX25_H4") (pintype "bidirectional+no_connect"))
    )
    (net (code "114") (name "unconnected-(U900-PX26-PadJ3)") (class "Default")
      (node (ref "U900") (pin "J3") (pinfunction "PX26_J3") (pintype "bidirectional+no_connect"))
    )
    (net (code "115") (name "unconnected-(U900-PX31-PadH5)") (class "Default")
      (node (ref "U900") (pin "H5") (pinfunction "PX31_H5") (pintype "bidirectional+no_connect"))
    )
  )
)
